# M8-Relay-Quad.net
KiCad netlist of a schematic drawn in EAGLE
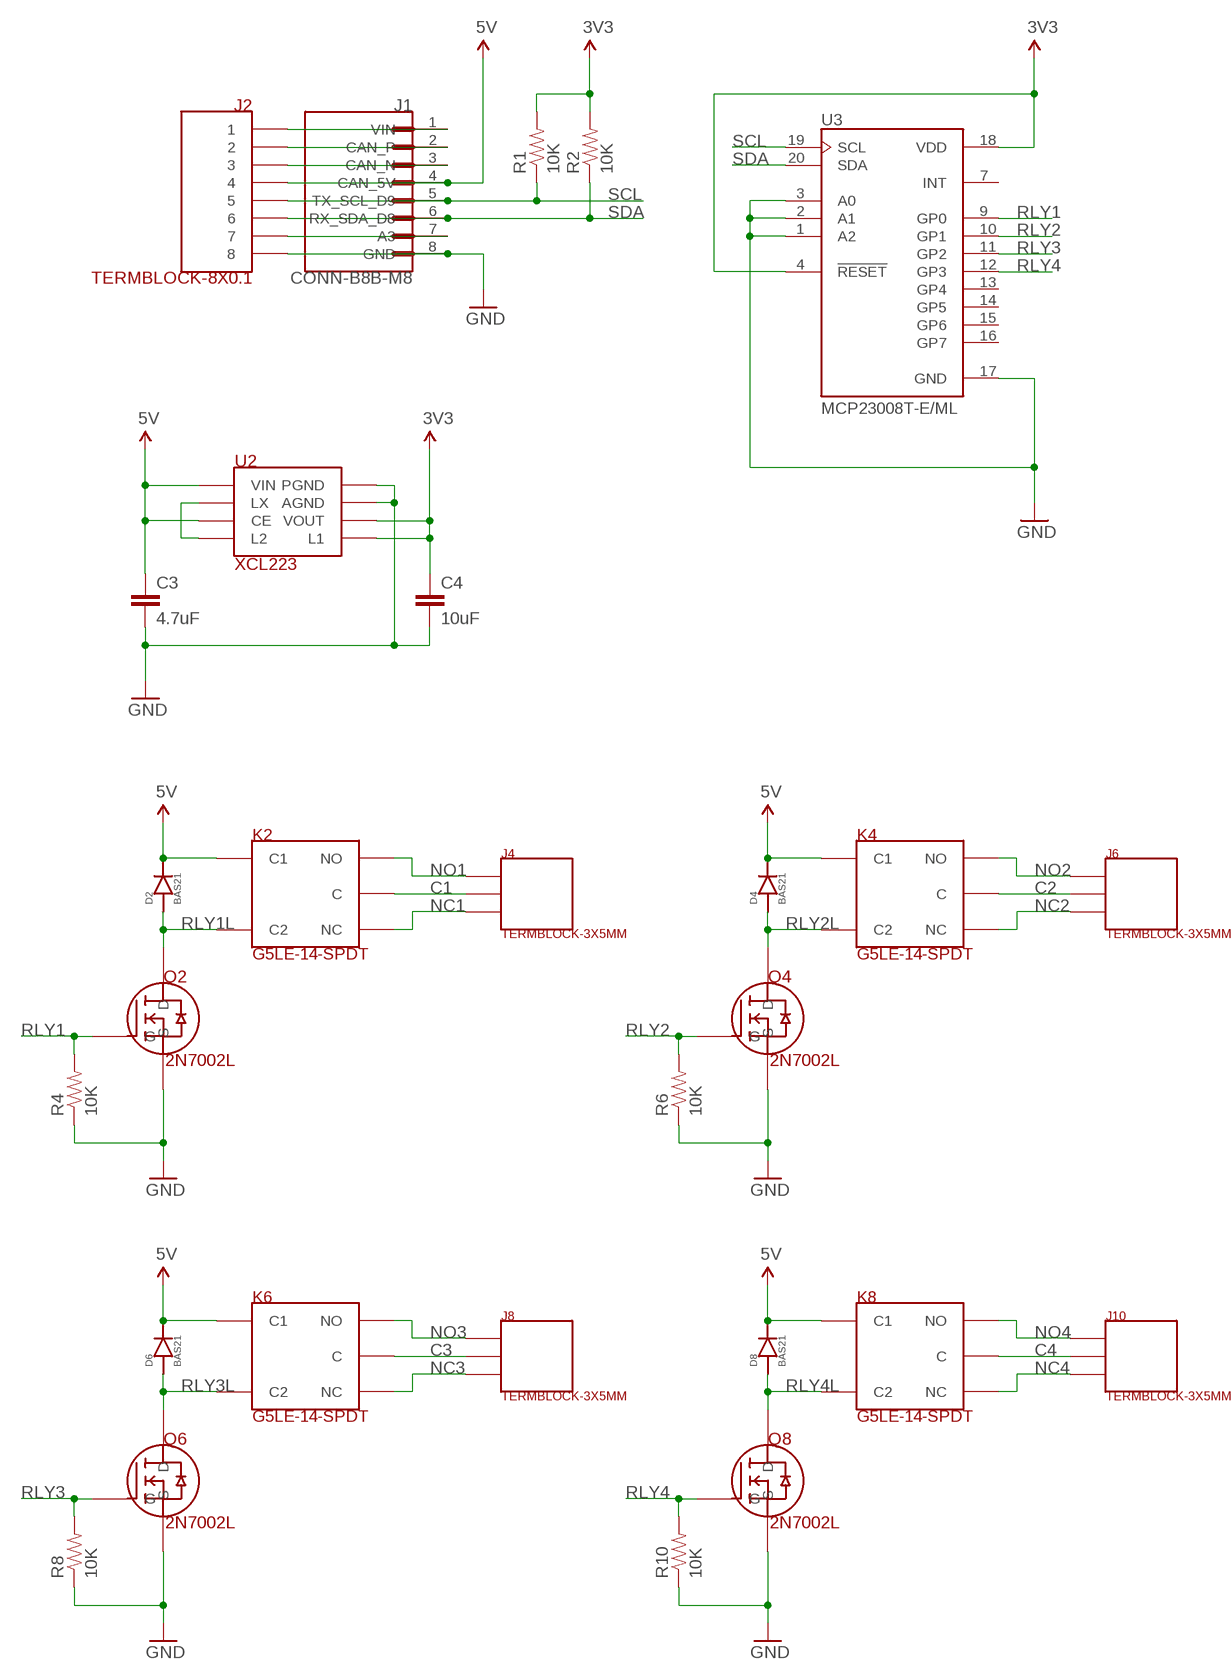
[diagram p0: schematic, sheet 1]

(export (version "E")
  (design (tool "Eeschema 10.0.6"))
  (components
    (comp (ref "C3")
      (value "4.7uF")
      (footprint "eagle-import:0603-CAP")
      (libsource (lib "eagle-import") (part "CAP-4.7UF-0603"))
    )
    (comp (ref "C4")
      (value "10uF")
      (footprint "eagle-import:0603-CAP")
      (libsource (lib "eagle-import") (part "CAP-10UF-0603"))
    )
    (comp (ref "D2")
      (value "BAS21")
      (footprint "eagle-import:DIODE-BAS21")
      (libsource (lib "eagle-import") (part "DIODE-BAS21"))
    )
    (comp (ref "D4")
      (value "BAS21")
      (footprint "eagle-import:DIODE-BAS21")
      (libsource (lib "eagle-import") (part "DIODE-BAS21"))
    )
    (comp (ref "D6")
      (value "BAS21")
      (footprint "eagle-import:DIODE-BAS21")
      (libsource (lib "eagle-import") (part "DIODE-BAS21"))
    )
    (comp (ref "D8")
      (value "BAS21")
      (footprint "eagle-import:DIODE-BAS21")
      (libsource (lib "eagle-import") (part "DIODE-BAS21"))
    )
    (comp (ref "J1")
      (value "CONN-B8B-M8")
      (footprint "eagle-import:JST_B8B-PH-SM4-TB(LF)(SN)")
      (libsource (lib "eagle-import") (part "CONN-B8B-M8"))
    )
    (comp (ref "J2")
      (value "TERMBLOCK-8X0.1")
      (footprint "eagle-import:TERMBLOCK-8X0.1")
      (libsource (lib "eagle-import") (part "TERMBLOCK-8X0.1"))
    )
    (comp (ref "J4")
      (value "TERMBLOCK-3X5MM")
      (footprint "eagle-import:TERMBLOCK-3X5MM")
      (libsource (lib "eagle-import") (part "TERMBLOCK-3X5MM"))
    )
    (comp (ref "J6")
      (value "TERMBLOCK-3X5MM")
      (footprint "eagle-import:TERMBLOCK-3X5MM")
      (libsource (lib "eagle-import") (part "TERMBLOCK-3X5MM"))
    )
    (comp (ref "J8")
      (value "TERMBLOCK-3X5MM")
      (footprint "eagle-import:TERMBLOCK-3X5MM")
      (libsource (lib "eagle-import") (part "TERMBLOCK-3X5MM"))
    )
    (comp (ref "J10")
      (value "TERMBLOCK-3X5MM")
      (footprint "eagle-import:TERMBLOCK-3X5MM")
      (libsource (lib "eagle-import") (part "TERMBLOCK-3X5MM"))
    )
    (comp (ref "K2")
      (value "G5LE-14-SPDT")
      (footprint "eagle-import:RELAY-G5LE-14-SPDT")
      (libsource (lib "eagle-import") (part "RELAY-G5LE-14-SPDT"))
    )
    (comp (ref "K4")
      (value "G5LE-14-SPDT")
      (footprint "eagle-import:RELAY-G5LE-14-SPDT")
      (libsource (lib "eagle-import") (part "RELAY-G5LE-14-SPDT"))
    )
    (comp (ref "K6")
      (value "G5LE-14-SPDT")
      (footprint "eagle-import:RELAY-G5LE-14-SPDT")
      (libsource (lib "eagle-import") (part "RELAY-G5LE-14-SPDT"))
    )
    (comp (ref "K8")
      (value "G5LE-14-SPDT")
      (footprint "eagle-import:RELAY-G5LE-14-SPDT")
      (libsource (lib "eagle-import") (part "RELAY-G5LE-14-SPDT"))
    )
    (comp (ref "Q2")
      (value "2N7002L")
      (footprint "eagle-import:2N7002L")
      (libsource (lib "eagle-import") (part "2N7002L"))
    )
    (comp (ref "Q4")
      (value "2N7002L")
      (footprint "eagle-import:2N7002L")
      (libsource (lib "eagle-import") (part "2N7002L"))
    )
    (comp (ref "Q6")
      (value "2N7002L")
      (footprint "eagle-import:2N7002L")
      (libsource (lib "eagle-import") (part "2N7002L"))
    )
    (comp (ref "Q8")
      (value "2N7002L")
      (footprint "eagle-import:2N7002L")
      (libsource (lib "eagle-import") (part "2N7002L"))
    )
    (comp (ref "R1")
      (value "10K")
      (footprint "eagle-import:0603-RES")
      (libsource (lib "eagle-import") (part "RES-10K-06030603"))
    )
    (comp (ref "R2")
      (value "10K")
      (footprint "eagle-import:0603-RES")
      (libsource (lib "eagle-import") (part "RES-10K-06030603"))
    )
    (comp (ref "R4")
      (value "10K")
      (footprint "eagle-import:0603-RES")
      (libsource (lib "eagle-import") (part "RES-10K-06030603"))
    )
    (comp (ref "R6")
      (value "10K")
      (footprint "eagle-import:0603-RES")
      (libsource (lib "eagle-import") (part "RES-10K-06030603"))
    )
    (comp (ref "R8")
      (value "10K")
      (footprint "eagle-import:0603-RES")
      (libsource (lib "eagle-import") (part "RES-10K-06030603"))
    )
    (comp (ref "R10")
      (value "10K")
      (footprint "eagle-import:0603-RES")
      (libsource (lib "eagle-import") (part "RES-10K-06030603"))
    )
    (comp (ref "U2")
      (value "XCL223")
      (footprint "eagle-import:REG-XCL223-LESS-CREAM")
      (libsource (lib "eagle-import") (part "REG-XCL223"))
    )
    (comp (ref "U3")
      (value "MCP23008T-E/ML")
      (footprint "eagle-import:QFN21P50_400X400X100L40X24T270N")
      (fields (field (name "MF") "Microchip Technology"))
      (libsource (lib "eagle-import") (part "MCP23008T-E/ML"))
    )
  )
  (nets
    (net (code "1") (name "/C1") (class "Default")
      (node (ref "J4") (pin "2") (pinfunction "2_2") (pintype "passive"))
      (node (ref "K2") (pin "1") (pinfunction "C_1") (pintype "passive"))
    )
    (net (code "2") (name "/C2") (class "Default")
      (node (ref "J6") (pin "2") (pinfunction "2_2") (pintype "passive"))
      (node (ref "K4") (pin "1") (pinfunction "C_1") (pintype "passive"))
    )
    (net (code "3") (name "/C3") (class "Default")
      (node (ref "J8") (pin "2") (pinfunction "2_2") (pintype "passive"))
      (node (ref "K6") (pin "1") (pinfunction "C_1") (pintype "passive"))
    )
    (net (code "4") (name "/C4") (class "Default")
      (node (ref "J10") (pin "2") (pinfunction "2_2") (pintype "passive"))
      (node (ref "K8") (pin "1") (pinfunction "C_1") (pintype "passive"))
    )
    (net (code "5") (name "/NC1") (class "Default")
      (node (ref "J4") (pin "3") (pinfunction "3_3") (pintype "passive"))
      (node (ref "K2") (pin "4") (pinfunction "NC_4") (pintype "passive"))
    )
    (net (code "6") (name "/NC2") (class "Default")
      (node (ref "J6") (pin "3") (pinfunction "3_3") (pintype "passive"))
      (node (ref "K4") (pin "4") (pinfunction "NC_4") (pintype "passive"))
    )
    (net (code "7") (name "/NC3") (class "Default")
      (node (ref "J8") (pin "3") (pinfunction "3_3") (pintype "passive"))
      (node (ref "K6") (pin "4") (pinfunction "NC_4") (pintype "passive"))
    )
    (net (code "8") (name "/NC4") (class "Default")
      (node (ref "J10") (pin "3") (pinfunction "3_3") (pintype "passive"))
      (node (ref "K8") (pin "4") (pinfunction "NC_4") (pintype "passive"))
    )
    (net (code "9") (name "/NO1") (class "Default")
      (node (ref "J4") (pin "1") (pinfunction "1_1") (pintype "passive"))
      (node (ref "K2") (pin "3") (pinfunction "NO_3") (pintype "passive"))
    )
    (net (code "10") (name "/NO2") (class "Default")
      (node (ref "J6") (pin "1") (pinfunction "1_1") (pintype "passive"))
      (node (ref "K4") (pin "3") (pinfunction "NO_3") (pintype "passive"))
    )
    (net (code "11") (name "/NO3") (class "Default")
      (node (ref "J8") (pin "1") (pinfunction "1_1") (pintype "passive"))
      (node (ref "K6") (pin "3") (pinfunction "NO_3") (pintype "passive"))
    )
    (net (code "12") (name "/NO4") (class "Default")
      (node (ref "J10") (pin "1") (pinfunction "1_1") (pintype "passive"))
      (node (ref "K8") (pin "3") (pinfunction "NO_3") (pintype "passive"))
    )
    (net (code "13") (name "/RLY1") (class "Default")
      (node (ref "Q2") (pin "1") (pinfunction "G_1") (pintype "bidirectional"))
      (node (ref "R4") (pin "2") (pinfunction "2_2") (pintype "passive"))
      (node (ref "U3") (pin "9") (pinfunction "GP0_9") (pintype "bidirectional"))
    )
    (net (code "14") (name "/RLY1L") (class "Default")
      (node (ref "D2") (pin "1") (pinfunction "ANODE_1") (pintype "bidirectional"))
      (node (ref "K2") (pin "5") (pinfunction "C2_5") (pintype "input"))
      (node (ref "Q2") (pin "3") (pinfunction "D_3") (pintype "bidirectional"))
    )
    (net (code "15") (name "/RLY2") (class "Default")
      (node (ref "Q4") (pin "1") (pinfunction "G_1") (pintype "bidirectional"))
      (node (ref "R6") (pin "2") (pinfunction "2_2") (pintype "passive"))
      (node (ref "U3") (pin "10") (pinfunction "GP1_10") (pintype "bidirectional"))
    )
    (net (code "16") (name "/RLY2L") (class "Default")
      (node (ref "D4") (pin "1") (pinfunction "ANODE_1") (pintype "bidirectional"))
      (node (ref "K4") (pin "5") (pinfunction "C2_5") (pintype "input"))
      (node (ref "Q4") (pin "3") (pinfunction "D_3") (pintype "bidirectional"))
    )
    (net (code "17") (name "/RLY3") (class "Default")
      (node (ref "Q6") (pin "1") (pinfunction "G_1") (pintype "bidirectional"))
      (node (ref "R8") (pin "2") (pinfunction "2_2") (pintype "passive"))
      (node (ref "U3") (pin "11") (pinfunction "GP2_11") (pintype "bidirectional"))
    )
    (net (code "18") (name "/RLY3L") (class "Default")
      (node (ref "D6") (pin "1") (pinfunction "ANODE_1") (pintype "bidirectional"))
      (node (ref "K6") (pin "5") (pinfunction "C2_5") (pintype "input"))
      (node (ref "Q6") (pin "3") (pinfunction "D_3") (pintype "bidirectional"))
    )
    (net (code "19") (name "/RLY4") (class "Default")
      (node (ref "Q8") (pin "1") (pinfunction "G_1") (pintype "bidirectional"))
      (node (ref "R10") (pin "2") (pinfunction "2_2") (pintype "passive"))
      (node (ref "U3") (pin "12") (pinfunction "GP3_12") (pintype "bidirectional"))
    )
    (net (code "20") (name "/RLY4L") (class "Default")
      (node (ref "D8") (pin "1") (pinfunction "ANODE_1") (pintype "bidirectional"))
      (node (ref "K8") (pin "5") (pinfunction "C2_5") (pintype "input"))
      (node (ref "Q8") (pin "3") (pinfunction "D_3") (pintype "bidirectional"))
    )
    (net (code "21") (name "/SCL") (class "Default")
      (node (ref "J1") (pin "5") (pinfunction "TX_SCL_D9_5") (pintype "passive"))
      (node (ref "J2") (pin "P$5") (pinfunction "5_P$5") (pintype "passive"))
      (node (ref "R1") (pin "1") (pinfunction "1_1") (pintype "passive"))
      (node (ref "U3") (pin "19") (pinfunction "SCL_19") (pintype "input"))
    )
    (net (code "22") (name "/SDA") (class "Default")
      (node (ref "J1") (pin "6") (pinfunction "RX_SDA_D8_6") (pintype "passive"))
      (node (ref "J2") (pin "P$6") (pinfunction "6_P$6") (pintype "passive"))
      (node (ref "R2") (pin "1") (pinfunction "1_1") (pintype "passive"))
      (node (ref "U3") (pin "20") (pinfunction "SDA_20") (pintype "bidirectional"))
    )
    (net (code "23") (name "3V3") (class "Default")
      (node (ref "C4") (pin "1") (pinfunction "1_1") (pintype "passive"))
      (node (ref "R1") (pin "2") (pinfunction "2_2") (pintype "passive"))
      (node (ref "R2") (pin "2") (pinfunction "2_2") (pintype "passive"))
      (node (ref "U2") (pin "3") (pinfunction "VOUT_3") (pintype "passive"))
      (node (ref "U2") (pin "7") (pinfunction "L1_7") (pintype "passive"))
      (node (ref "U3") (pin "18") (pinfunction "VDD_18") (pintype "power_in"))
      (node (ref "U3") (pin "4") (pinfunction "~{RESET}_4") (pintype "input"))
    )
    (net (code "24") (name "5V") (class "Default")
      (node (ref "C3") (pin "1") (pinfunction "1_1") (pintype "passive"))
      (node (ref "D2") (pin "3") (pinfunction "CATHODE_3") (pintype "bidirectional"))
      (node (ref "D4") (pin "3") (pinfunction "CATHODE_3") (pintype "bidirectional"))
      (node (ref "D6") (pin "3") (pinfunction "CATHODE_3") (pintype "bidirectional"))
      (node (ref "D8") (pin "3") (pinfunction "CATHODE_3") (pintype "bidirectional"))
      (node (ref "J1") (pin "4") (pinfunction "CAN_5V_4") (pintype "passive"))
      (node (ref "J2") (pin "P$4") (pinfunction "4_P$4") (pintype "passive"))
      (node (ref "K2") (pin "2") (pinfunction "C1_2") (pintype "input"))
      (node (ref "K4") (pin "2") (pinfunction "C1_2") (pintype "input"))
      (node (ref "K6") (pin "2") (pinfunction "C1_2") (pintype "input"))
      (node (ref "K8") (pin "2") (pinfunction "C1_2") (pintype "input"))
      (node (ref "U2") (pin "4") (pinfunction "CE_4") (pintype "input"))
      (node (ref "U2") (pin "6") (pinfunction "VIN_6") (pintype "power_in"))
    )
    (net (code "25") (name "GND") (class "Default")
      (node (ref "C3") (pin "2") (pinfunction "2_2") (pintype "passive"))
      (node (ref "C4") (pin "2") (pinfunction "2_2") (pintype "passive"))
      (node (ref "J1") (pin "8") (pinfunction "GND_8") (pintype "passive"))
      (node (ref "J2") (pin "P$8") (pinfunction "8_P$8") (pintype "passive"))
      (node (ref "Q2") (pin "2") (pinfunction "S_2") (pintype "bidirectional"))
      (node (ref "Q4") (pin "2") (pinfunction "S_2") (pintype "bidirectional"))
      (node (ref "Q6") (pin "2") (pinfunction "S_2") (pintype "bidirectional"))
      (node (ref "Q8") (pin "2") (pinfunction "S_2") (pintype "bidirectional"))
      (node (ref "R10") (pin "1") (pinfunction "1_1") (pintype "passive"))
      (node (ref "R4") (pin "1") (pinfunction "1_1") (pintype "passive"))
      (node (ref "R6") (pin "1") (pinfunction "1_1") (pintype "passive"))
      (node (ref "R8") (pin "1") (pinfunction "1_1") (pintype "passive"))
      (node (ref "U2") (pin "1") (pinfunction "PGND_1") (pintype "passive"))
      (node (ref "U2") (pin "2") (pinfunction "AGND_2") (pintype "passive"))
      (node (ref "U3") (pin "1") (pinfunction "A2_1") (pintype "bidirectional"))
      (node (ref "U3") (pin "17") (pinfunction "GND_17") (pintype "power_in"))
      (node (ref "U3") (pin "2") (pinfunction "A1_2") (pintype "input"))
      (node (ref "U3") (pin "3") (pinfunction "A0_3") (pintype "input"))
    )
    (net (code "26") (name "Net-(J1-A3)") (class "Default")
      (node (ref "J1") (pin "7") (pinfunction "A3_7") (pintype "passive"))
      (node (ref "J2") (pin "P$7") (pinfunction "7_P$7") (pintype "passive"))
    )
    (net (code "27") (name "Net-(J1-CAN_N)") (class "Default")
      (node (ref "J1") (pin "3") (pinfunction "CAN_N_3") (pintype "passive"))
      (node (ref "J2") (pin "P$3") (pinfunction "3_P$3") (pintype "passive"))
    )
    (net (code "28") (name "Net-(J1-CAN_P)") (class "Default")
      (node (ref "J1") (pin "2") (pinfunction "CAN_P_2") (pintype "passive"))
      (node (ref "J2") (pin "P$2") (pinfunction "2_P$2") (pintype "passive"))
    )
    (net (code "29") (name "Net-(J1-VIN)") (class "Default")
      (node (ref "J1") (pin "1") (pinfunction "VIN_1") (pintype "passive"))
      (node (ref "J2") (pin "P$1") (pinfunction "1_P$1") (pintype "passive"))
    )
    (net (code "30") (name "Net-(U2-L2)") (class "Default")
      (node (ref "U2") (pin "5") (pinfunction "LX_5") (pintype "passive"))
      (node (ref "U2") (pin "8") (pinfunction "L2_8") (pintype "passive"))
    )
    (net (code "31") (name "unconnected-(U3-GP4-Pad13)") (class "Default")
      (node (ref "U3") (pin "13") (pinfunction "GP4_13") (pintype "bidirectional"))
    )
    (net (code "32") (name "unconnected-(U3-GP5-Pad14)") (class "Default")
      (node (ref "U3") (pin "14") (pinfunction "GP5_14") (pintype "bidirectional"))
    )
    (net (code "33") (name "unconnected-(U3-GP6-Pad15)") (class "Default")
      (node (ref "U3") (pin "15") (pinfunction "GP6_15") (pintype "bidirectional"))
    )
    (net (code "34") (name "unconnected-(U3-GP7-Pad16)") (class "Default")
      (node (ref "U3") (pin "16") (pinfunction "GP7_16") (pintype "bidirectional"))
    )
    (net (code "35") (name "unconnected-(U3-INT-Pad7)") (class "Default")
      (node (ref "U3") (pin "7") (pinfunction "INT_7") (pintype "output"))
    )
  )
)
